# 07_-_SAMA7D65-PIO.net
KiCad netlist of a schematic drawn in Altium Designer
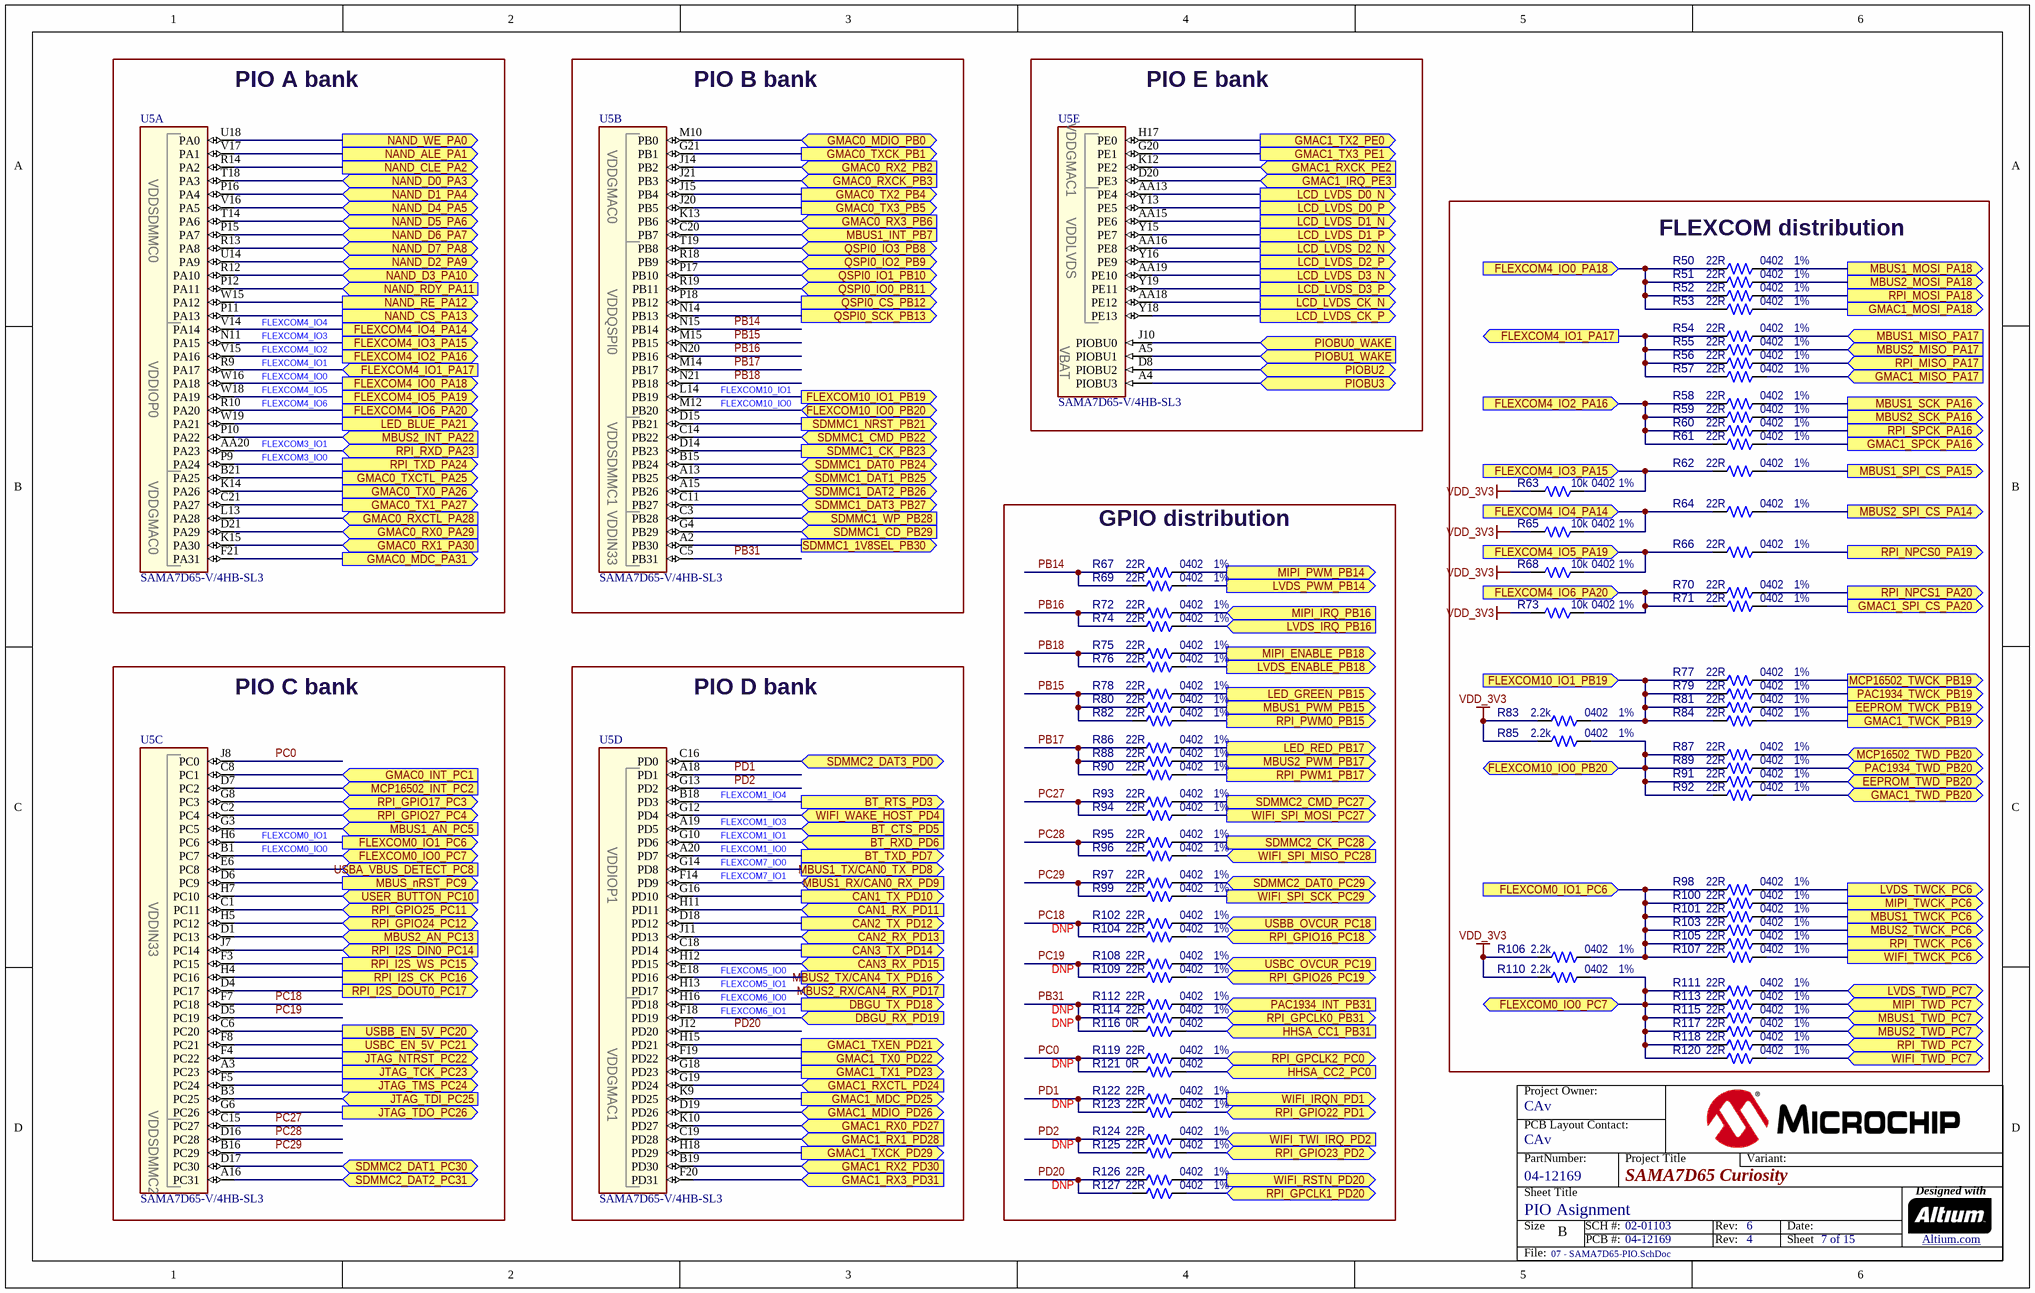
[diagram p0: 07 - SAMA7D65-PIO.SchDoc]

(export (version "E")
  (design (tool "Eeschema 10.0.6"))
  (components
    (comp (ref "R50")
      (value "22R")
      (footprint "RES_C_0402")
      (description "Resistor")
      (fields
        (field (name "PACKAGE") "0402")
        (field (name "POWER") "1/10W")
        (field (name "TOLERANCE") "1%")
        (field (name "OWNER") "Mike Ragsdale")
      )
      (libsource (lib "") (part "Resistor_1"))
    )
    (comp (ref "R51")
      (value "22R")
      (footprint "RES_C_0402")
      (description "Resistor")
      (fields
        (field (name "PACKAGE") "0402")
        (field (name "POWER") "1/10W")
        (field (name "TOLERANCE") "1%")
        (field (name "OWNER") "Mike Ragsdale")
      )
      (libsource (lib "") (part "Resistor_1"))
    )
    (comp (ref "R52")
      (value "22R")
      (footprint "RES_C_0402")
      (description "Resistor")
      (fields
        (field (name "PACKAGE") "0402")
        (field (name "POWER") "1/10W")
        (field (name "TOLERANCE") "1%")
        (field (name "OWNER") "Mike Ragsdale")
      )
      (libsource (lib "") (part "Resistor_1"))
    )
    (comp (ref "R53")
      (value "22R")
      (footprint "RES_C_0402")
      (description "Resistor")
      (fields
        (field (name "PACKAGE") "0402")
        (field (name "POWER") "1/10W")
        (field (name "TOLERANCE") "1%")
        (field (name "OWNER") "Mike Ragsdale")
      )
      (libsource (lib "") (part "Resistor_1"))
    )
    (comp (ref "R54")
      (value "22R")
      (footprint "RES_C_0402")
      (description "Resistor")
      (fields
        (field (name "PACKAGE") "0402")
        (field (name "POWER") "1/10W")
        (field (name "TOLERANCE") "1%")
        (field (name "OWNER") "Mike Ragsdale")
      )
      (libsource (lib "") (part "Resistor_1"))
    )
    (comp (ref "R55")
      (value "22R")
      (footprint "RES_C_0402")
      (description "Resistor")
      (fields
        (field (name "PACKAGE") "0402")
        (field (name "POWER") "1/10W")
        (field (name "TOLERANCE") "1%")
        (field (name "OWNER") "Mike Ragsdale")
      )
      (libsource (lib "") (part "Resistor_1"))
    )
    (comp (ref "R56")
      (value "22R")
      (footprint "RES_C_0402")
      (description "Resistor")
      (fields
        (field (name "PACKAGE") "0402")
        (field (name "POWER") "1/10W")
        (field (name "TOLERANCE") "1%")
        (field (name "OWNER") "Mike Ragsdale")
      )
      (libsource (lib "") (part "Resistor_1"))
    )
    (comp (ref "R57")
      (value "22R")
      (footprint "RES_C_0402")
      (description "Resistor")
      (fields
        (field (name "PACKAGE") "0402")
        (field (name "POWER") "1/10W")
        (field (name "TOLERANCE") "1%")
        (field (name "OWNER") "Mike Ragsdale")
      )
      (libsource (lib "") (part "Resistor_1"))
    )
    (comp (ref "R58")
      (value "22R")
      (footprint "RES_C_0402")
      (description "Resistor")
      (fields
        (field (name "PACKAGE") "0402")
        (field (name "POWER") "1/10W")
        (field (name "TOLERANCE") "1%")
        (field (name "OWNER") "Mike Ragsdale")
      )
      (libsource (lib "") (part "Resistor_1"))
    )
    (comp (ref "R59")
      (value "22R")
      (footprint "RES_C_0402")
      (description "Resistor")
      (fields
        (field (name "PACKAGE") "0402")
        (field (name "POWER") "1/10W")
        (field (name "TOLERANCE") "1%")
        (field (name "OWNER") "Mike Ragsdale")
      )
      (libsource (lib "") (part "Resistor_1"))
    )
    (comp (ref "R60")
      (value "22R")
      (footprint "RES_C_0402")
      (description "Resistor")
      (fields
        (field (name "PACKAGE") "0402")
        (field (name "POWER") "1/10W")
        (field (name "TOLERANCE") "1%")
        (field (name "OWNER") "Mike Ragsdale")
      )
      (libsource (lib "") (part "Resistor_1"))
    )
    (comp (ref "R61")
      (value "22R")
      (footprint "RES_C_0402")
      (description "Resistor")
      (fields
        (field (name "PACKAGE") "0402")
        (field (name "POWER") "1/10W")
        (field (name "TOLERANCE") "1%")
        (field (name "OWNER") "Mike Ragsdale")
      )
      (libsource (lib "") (part "Resistor_1"))
    )
    (comp (ref "R62")
      (value "22R")
      (footprint "RES_C_0402")
      (description "Resistor")
      (fields
        (field (name "PACKAGE") "0402")
        (field (name "POWER") "1/10W")
        (field (name "TOLERANCE") "1%")
        (field (name "OWNER") "Mike Ragsdale")
      )
      (libsource (lib "") (part "Resistor_1"))
    )
    (comp (ref "R63")
      (value "10k")
      (footprint "RES_C_0402")
      (description "Resistor")
      (fields
        (field (name "PACKAGE") "0402")
        (field (name "TOLERANCE") "1%")
        (field (name "VOLTAGE") "50V")
        (field (name "POWER") "1/10W")
        (field (name "OWNER") "Brent Lanphear")
      )
      (libsource (lib "MCHP-CDB") (part "Resistor"))
    )
    (comp (ref "R64")
      (value "22R")
      (footprint "RES_C_0402")
      (description "Resistor")
      (fields
        (field (name "PACKAGE") "0402")
        (field (name "POWER") "1/10W")
        (field (name "TOLERANCE") "1%")
        (field (name "OWNER") "Mike Ragsdale")
      )
      (libsource (lib "") (part "Resistor_1"))
    )
    (comp (ref "R65")
      (value "10k")
      (footprint "RES_C_0402")
      (description "Resistor")
      (fields
        (field (name "PACKAGE") "0402")
        (field (name "TOLERANCE") "1%")
        (field (name "VOLTAGE") "50V")
        (field (name "POWER") "1/10W")
        (field (name "OWNER") "Brent Lanphear")
      )
      (libsource (lib "MCHP-CDB") (part "Resistor"))
    )
    (comp (ref "R66")
      (value "22R")
      (footprint "RES_C_0402")
      (description "Resistor")
      (fields
        (field (name "PACKAGE") "0402")
        (field (name "POWER") "1/10W")
        (field (name "TOLERANCE") "1%")
        (field (name "OWNER") "Mike Ragsdale")
      )
      (libsource (lib "") (part "Resistor_1"))
    )
    (comp (ref "R67")
      (value "22R")
      (footprint "RES_C_0402")
      (description "Resistor")
      (fields
        (field (name "PACKAGE") "0402")
        (field (name "POWER") "1/10W")
        (field (name "TOLERANCE") "1%")
        (field (name "OWNER") "Mike Ragsdale")
      )
      (libsource (lib "") (part "Resistor_1"))
    )
    (comp (ref "R68")
      (value "10k")
      (footprint "RES_C_0402")
      (description "Resistor")
      (fields
        (field (name "PACKAGE") "0402")
        (field (name "TOLERANCE") "1%")
        (field (name "VOLTAGE") "50V")
        (field (name "POWER") "1/10W")
        (field (name "OWNER") "Brent Lanphear")
      )
      (libsource (lib "MCHP-CDB") (part "Resistor"))
    )
    (comp (ref "R69")
      (value "22R")
      (footprint "RES_C_0402")
      (description "Resistor")
      (fields
        (field (name "PACKAGE") "0402")
        (field (name "POWER") "1/10W")
        (field (name "TOLERANCE") "1%")
        (field (name "OWNER") "Mike Ragsdale")
      )
      (libsource (lib "") (part "Resistor_1"))
    )
    (comp (ref "R70")
      (value "22R")
      (footprint "RES_C_0402")
      (description "Resistor")
      (fields
        (field (name "PACKAGE") "0402")
        (field (name "POWER") "1/10W")
        (field (name "TOLERANCE") "1%")
        (field (name "OWNER") "Mike Ragsdale")
      )
      (libsource (lib "") (part "Resistor_1"))
    )
    (comp (ref "R71")
      (value "22R")
      (footprint "RES_C_0402")
      (description "Resistor")
      (fields
        (field (name "PACKAGE") "0402")
        (field (name "POWER") "1/10W")
        (field (name "TOLERANCE") "1%")
        (field (name "OWNER") "Mike Ragsdale")
      )
      (libsource (lib "") (part "Resistor_1"))
    )
    (comp (ref "R72")
      (value "22R")
      (footprint "RES_C_0402")
      (description "Resistor")
      (fields
        (field (name "PACKAGE") "0402")
        (field (name "POWER") "1/10W")
        (field (name "TOLERANCE") "1%")
        (field (name "OWNER") "Mike Ragsdale")
      )
      (libsource (lib "") (part "Resistor_1"))
    )
    (comp (ref "R73")
      (value "10k")
      (footprint "RES_C_0402")
      (description "Resistor")
      (fields
        (field (name "PACKAGE") "0402")
        (field (name "TOLERANCE") "1%")
        (field (name "VOLTAGE") "50V")
        (field (name "POWER") "1/10W")
        (field (name "OWNER") "Brent Lanphear")
      )
      (libsource (lib "MCHP-CDB") (part "Resistor"))
    )
    (comp (ref "R74")
      (value "22R")
      (footprint "RES_C_0402")
      (description "Resistor")
      (fields
        (field (name "PACKAGE") "0402")
        (field (name "POWER") "1/10W")
        (field (name "TOLERANCE") "1%")
        (field (name "OWNER") "Mike Ragsdale")
      )
      (libsource (lib "") (part "Resistor_1"))
    )
    (comp (ref "R75")
      (value "22R")
      (footprint "RES_C_0402")
      (description "Resistor")
      (fields
        (field (name "PACKAGE") "0402")
        (field (name "POWER") "1/10W")
        (field (name "TOLERANCE") "1%")
        (field (name "OWNER") "Mike Ragsdale")
      )
      (libsource (lib "") (part "Resistor_1"))
    )
    (comp (ref "R76")
      (value "22R")
      (footprint "RES_C_0402")
      (description "Resistor")
      (fields
        (field (name "PACKAGE") "0402")
        (field (name "POWER") "1/10W")
        (field (name "TOLERANCE") "1%")
        (field (name "OWNER") "Mike Ragsdale")
      )
      (libsource (lib "") (part "Resistor_1"))
    )
    (comp (ref "R77")
      (value "22R")
      (footprint "RES_C_0402")
      (description "Resistor")
      (fields
        (field (name "PACKAGE") "0402")
        (field (name "POWER") "1/10W")
        (field (name "TOLERANCE") "1%")
        (field (name "OWNER") "Mike Ragsdale")
      )
      (libsource (lib "") (part "Resistor_1"))
    )
    (comp (ref "R78")
      (value "22R")
      (footprint "RES_C_0402")
      (description "Resistor")
      (fields
        (field (name "PACKAGE") "0402")
        (field (name "POWER") "1/10W")
        (field (name "TOLERANCE") "1%")
        (field (name "OWNER") "Mike Ragsdale")
      )
      (libsource (lib "") (part "Resistor_1"))
    )
    (comp (ref "R79")
      (value "22R")
      (footprint "RES_C_0402")
      (description "Resistor")
      (fields
        (field (name "PACKAGE") "0402")
        (field (name "POWER") "1/10W")
        (field (name "TOLERANCE") "1%")
        (field (name "OWNER") "Mike Ragsdale")
      )
      (libsource (lib "") (part "Resistor_1"))
    )
    (comp (ref "R80")
      (value "22R")
      (footprint "RES_C_0402")
      (description "Resistor")
      (fields
        (field (name "PACKAGE") "0402")
        (field (name "POWER") "1/10W")
        (field (name "TOLERANCE") "1%")
        (field (name "OWNER") "Mike Ragsdale")
      )
      (libsource (lib "") (part "Resistor_1"))
    )
    (comp (ref "R81")
      (value "22R")
      (footprint "RES_C_0402")
      (description "Resistor")
      (fields
        (field (name "PACKAGE") "0402")
        (field (name "POWER") "1/10W")
        (field (name "TOLERANCE") "1%")
        (field (name "OWNER") "Mike Ragsdale")
      )
      (libsource (lib "") (part "Resistor_1"))
    )
    (comp (ref "R82")
      (value "22R")
      (footprint "RES_C_0402")
      (description "Resistor")
      (fields
        (field (name "PACKAGE") "0402")
        (field (name "POWER") "1/10W")
        (field (name "TOLERANCE") "1%")
        (field (name "OWNER") "Mike Ragsdale")
      )
      (libsource (lib "") (part "Resistor_1"))
    )
    (comp (ref "R83")
      (value "2.2k")
      (footprint "RES_C_0402")
      (description "Resistor")
      (fields
        (field (name "PACKAGE") "0402")
        (field (name "POWER") "1/10W")
        (field (name "TOLERANCE") "1%")
        (field (name "VOLTAGE") "50V")
        (field (name "OWNER") "Tad Ahlvers")
      )
      (libsource (lib "") (part "Resistor_1"))
    )
    (comp (ref "R84")
      (value "22R")
      (footprint "RES_C_0402")
      (description "Resistor")
      (fields
        (field (name "PACKAGE") "0402")
        (field (name "POWER") "1/10W")
        (field (name "TOLERANCE") "1%")
        (field (name "OWNER") "Mike Ragsdale")
      )
      (libsource (lib "") (part "Resistor_1"))
    )
    (comp (ref "R85")
      (value "2.2k")
      (footprint "RES_C_0402")
      (description "Resistor")
      (fields
        (field (name "PACKAGE") "0402")
        (field (name "POWER") "1/10W")
        (field (name "TOLERANCE") "1%")
        (field (name "VOLTAGE") "50V")
        (field (name "OWNER") "Tad Ahlvers")
      )
      (libsource (lib "") (part "Resistor_1"))
    )
    (comp (ref "R86")
      (value "22R")
      (footprint "RES_C_0402")
      (description "Resistor")
      (fields
        (field (name "PACKAGE") "0402")
        (field (name "POWER") "1/10W")
        (field (name "TOLERANCE") "1%")
        (field (name "OWNER") "Mike Ragsdale")
      )
      (libsource (lib "") (part "Resistor_1"))
    )
    (comp (ref "R87")
      (value "22R")
      (footprint "RES_C_0402")
      (description "Resistor")
      (fields
        (field (name "PACKAGE") "0402")
        (field (name "POWER") "1/10W")
        (field (name "TOLERANCE") "1%")
        (field (name "OWNER") "Mike Ragsdale")
      )
      (libsource (lib "") (part "Resistor_1"))
    )
    (comp (ref "R88")
      (value "22R")
      (footprint "RES_C_0402")
      (description "Resistor")
      (fields
        (field (name "PACKAGE") "0402")
        (field (name "POWER") "1/10W")
        (field (name "TOLERANCE") "1%")
        (field (name "OWNER") "Mike Ragsdale")
      )
      (libsource (lib "") (part "Resistor_1"))
    )
    (comp (ref "R89")
      (value "22R")
      (footprint "RES_C_0402")
      (description "Resistor")
      (fields
        (field (name "PACKAGE") "0402")
        (field (name "POWER") "1/10W")
        (field (name "TOLERANCE") "1%")
        (field (name "OWNER") "Mike Ragsdale")
      )
      (libsource (lib "") (part "Resistor_1"))
    )
    (comp (ref "R90")
      (value "22R")
      (footprint "RES_C_0402")
      (description "Resistor")
      (fields
        (field (name "PACKAGE") "0402")
        (field (name "POWER") "1/10W")
        (field (name "TOLERANCE") "1%")
        (field (name "OWNER") "Mike Ragsdale")
      )
      (libsource (lib "") (part "Resistor_1"))
    )
    (comp (ref "R91")
      (value "22R")
      (footprint "RES_C_0402")
      (description "Resistor")
      (fields
        (field (name "PACKAGE") "0402")
        (field (name "POWER") "1/10W")
        (field (name "TOLERANCE") "1%")
        (field (name "OWNER") "Mike Ragsdale")
      )
      (libsource (lib "") (part "Resistor_1"))
    )
    (comp (ref "R92")
      (value "22R")
      (footprint "RES_C_0402")
      (description "Resistor")
      (fields
        (field (name "PACKAGE") "0402")
        (field (name "POWER") "1/10W")
        (field (name "TOLERANCE") "1%")
        (field (name "OWNER") "Mike Ragsdale")
      )
      (libsource (lib "") (part "Resistor_1"))
    )
    (comp (ref "R93")
      (value "22R")
      (footprint "RES_C_0402")
      (description "Resistor")
      (fields
        (field (name "PACKAGE") "0402")
        (field (name "POWER") "1/10W")
        (field (name "TOLERANCE") "1%")
        (field (name "OWNER") "Mike Ragsdale")
      )
      (libsource (lib "") (part "Resistor_1"))
    )
    (comp (ref "R94")
      (value "22R")
      (footprint "RES_C_0402")
      (description "Resistor")
      (fields
        (field (name "PACKAGE") "0402")
        (field (name "POWER") "1/10W")
        (field (name "TOLERANCE") "1%")
        (field (name "OWNER") "Mike Ragsdale")
      )
      (libsource (lib "") (part "Resistor_1"))
    )
    (comp (ref "R95")
      (value "22R")
      (footprint "RES_C_0402")
      (description "Resistor")
      (fields
        (field (name "PACKAGE") "0402")
        (field (name "POWER") "1/10W")
        (field (name "TOLERANCE") "1%")
        (field (name "OWNER") "Mike Ragsdale")
      )
      (libsource (lib "") (part "Resistor_1"))
    )
    (comp (ref "R96")
      (value "22R")
      (footprint "RES_C_0402")
      (description "Resistor")
      (fields
        (field (name "PACKAGE") "0402")
        (field (name "POWER") "1/10W")
        (field (name "TOLERANCE") "1%")
        (field (name "OWNER") "Mike Ragsdale")
      )
      (libsource (lib "") (part "Resistor_1"))
    )
    (comp (ref "R97")
      (value "22R")
      (footprint "RES_C_0402")
      (description "Resistor")
      (fields
        (field (name "PACKAGE") "0402")
        (field (name "POWER") "1/10W")
        (field (name "TOLERANCE") "1%")
        (field (name "OWNER") "Mike Ragsdale")
      )
      (libsource (lib "") (part "Resistor_1"))
    )
    (comp (ref "R98")
      (value "22R")
      (footprint "RES_C_0402")
      (description "Resistor")
      (fields
        (field (name "PACKAGE") "0402")
        (field (name "POWER") "1/10W")
        (field (name "TOLERANCE") "1%")
        (field (name "OWNER") "Mike Ragsdale")
      )
      (libsource (lib "") (part "Resistor_1"))
    )
    (comp (ref "R99")
      (value "22R")
      (footprint "RES_C_0402")
      (description "Resistor")
      (fields
        (field (name "PACKAGE") "0402")
        (field (name "POWER") "1/10W")
        (field (name "TOLERANCE") "1%")
        (field (name "OWNER") "Mike Ragsdale")
      )
      (libsource (lib "") (part "Resistor_1"))
    )
    (comp (ref "R100")
      (value "22R")
      (footprint "RES_C_0402")
      (description "Resistor")
      (fields
        (field (name "PACKAGE") "0402")
        (field (name "POWER") "1/10W")
        (field (name "TOLERANCE") "1%")
        (field (name "OWNER") "Mike Ragsdale")
      )
      (libsource (lib "") (part "Resistor_1"))
    )
    (comp (ref "R101")
      (value "22R")
      (footprint "RES_C_0402")
      (description "Resistor")
      (fields
        (field (name "PACKAGE") "0402")
        (field (name "POWER") "1/10W")
        (field (name "TOLERANCE") "1%")
        (field (name "OWNER") "Mike Ragsdale")
      )
      (libsource (lib "") (part "Resistor_1"))
    )
    (comp (ref "R102")
      (value "22R")
      (footprint "RES_C_0402")
      (description "Resistor")
      (fields
        (field (name "PACKAGE") "0402")
        (field (name "POWER") "1/10W")
        (field (name "TOLERANCE") "1%")
        (field (name "OWNER") "Mike Ragsdale")
      )
      (libsource (lib "") (part "Resistor_1"))
    )
    (comp (ref "R103")
      (value "22R")
      (footprint "RES_C_0402")
      (description "Resistor")
      (fields
        (field (name "PACKAGE") "0402")
        (field (name "POWER") "1/10W")
        (field (name "TOLERANCE") "1%")
        (field (name "OWNER") "Mike Ragsdale")
      )
      (libsource (lib "") (part "Resistor_1"))
    )
    (comp (ref "R104")
      (value "22R")
      (footprint "RES_C_0402")
      (description "Resistor")
      (fields
        (field (name "PACKAGE") "0402")
        (field (name "POWER") "1/10W")
        (field (name "POPULATED") "DNP")
        (field (name "TOLERANCE") "1%")
        (field (name "OWNER") "Mike Ragsdale")
      )
      (libsource (lib "") (part "Resistor_1"))
    )
    (comp (ref "R105")
      (value "22R")
      (footprint "RES_C_0402")
      (description "Resistor")
      (fields
        (field (name "PACKAGE") "0402")
        (field (name "POWER") "1/10W")
        (field (name "TOLERANCE") "1%")
        (field (name "OWNER") "Mike Ragsdale")
      )
      (libsource (lib "") (part "Resistor_1"))
    )
    (comp (ref "R106")
      (value "2.2k")
      (footprint "RES_C_0402")
      (description "Resistor")
      (fields
        (field (name "PACKAGE") "0402")
        (field (name "POWER") "1/10W")
        (field (name "TOLERANCE") "1%")
        (field (name "VOLTAGE") "50V")
        (field (name "OWNER") "Tad Ahlvers")
      )
      (libsource (lib "") (part "Resistor_1"))
    )
    (comp (ref "R107")
      (value "22R")
      (footprint "RES_C_0402")
      (description "Resistor")
      (fields
        (field (name "PACKAGE") "0402")
        (field (name "POWER") "1/10W")
        (field (name "TOLERANCE") "1%")
        (field (name "OWNER") "Mike Ragsdale")
      )
      (libsource (lib "") (part "Resistor_1"))
    )
    (comp (ref "R108")
      (value "22R")
      (footprint "RES_C_0402")
      (description "Resistor")
      (fields
        (field (name "PACKAGE") "0402")
        (field (name "POWER") "1/10W")
        (field (name "TOLERANCE") "1%")
        (field (name "OWNER") "Mike Ragsdale")
      )
      (libsource (lib "") (part "Resistor_1"))
    )
    (comp (ref "R109")
      (value "22R")
      (footprint "RES_C_0402")
      (description "Resistor")
      (fields
        (field (name "PACKAGE") "0402")
        (field (name "POWER") "1/10W")
        (field (name "POPULATED") "DNP")
        (field (name "TOLERANCE") "1%")
        (field (name "OWNER") "Mike Ragsdale")
      )
      (libsource (lib "") (part "Resistor_1"))
    )
    (comp (ref "R110")
      (value "2.2k")
      (footprint "RES_C_0402")
      (description "Resistor")
      (fields
        (field (name "PACKAGE") "0402")
        (field (name "POWER") "1/10W")
        (field (name "TOLERANCE") "1%")
        (field (name "VOLTAGE") "50V")
        (field (name "OWNER") "Tad Ahlvers")
      )
      (libsource (lib "") (part "Resistor_1"))
    )
    (comp (ref "R111")
      (value "22R")
      (footprint "RES_C_0402")
      (description "Resistor")
      (fields
        (field (name "PACKAGE") "0402")
        (field (name "POWER") "1/10W")
        (field (name "TOLERANCE") "1%")
        (field (name "OWNER") "Mike Ragsdale")
      )
      (libsource (lib "") (part "Resistor_1"))
    )
    (comp (ref "R112")
      (value "22R")
      (footprint "RES_C_0402")
      (description "Resistor")
      (fields
        (field (name "PACKAGE") "0402")
        (field (name "POWER") "1/10W")
        (field (name "TOLERANCE") "1%")
        (field (name "OWNER") "Mike Ragsdale")
      )
      (libsource (lib "") (part "Resistor_1"))
    )
    (comp (ref "R113")
      (value "22R")
      (footprint "RES_C_0402")
      (description "Resistor")
      (fields
        (field (name "PACKAGE") "0402")
        (field (name "POWER") "1/10W")
        (field (name "TOLERANCE") "1%")
        (field (name "OWNER") "Mike Ragsdale")
      )
      (libsource (lib "") (part "Resistor_1"))
    )
    (comp (ref "R114")
      (value "22R")
      (footprint "RES_C_0402")
      (description "Resistor")
      (fields
        (field (name "PACKAGE") "0402")
        (field (name "POWER") "1/10W")
        (field (name "POPULATED") "DNP")
        (field (name "TOLERANCE") "1%")
        (field (name "OWNER") "Mike Ragsdale")
      )
      (libsource (lib "") (part "Resistor_1"))
    )
    (comp (ref "R115")
      (value "22R")
      (footprint "RES_C_0402")
      (description "Resistor")
      (fields
        (field (name "PACKAGE") "0402")
        (field (name "POWER") "1/10W")
        (field (name "TOLERANCE") "1%")
        (field (name "OWNER") "Mike Ragsdale")
      )
      (libsource (lib "") (part "Resistor_1"))
    )
    (comp (ref "R116")
      (value "0R")
      (footprint "RES_C_0402")
      (description "Resistor")
      (fields
        (field (name "PACKAGE") "0402")
        (field (name "POWER") "1/16W")
        (field (name "POPULATED") "DNP")
        (field (name "OWNER") "Sompoch Loboonlert")
      )
      (libsource (lib "") (part "Resistor_1"))
    )
    (comp (ref "R117")
      (value "22R")
      (footprint "RES_C_0402")
      (description "Resistor")
      (fields
        (field (name "PACKAGE") "0402")
        (field (name "POWER") "1/10W")
        (field (name "TOLERANCE") "1%")
        (field (name "OWNER") "Mike Ragsdale")
      )
      (libsource (lib "") (part "Resistor_1"))
    )
    (comp (ref "R118")
      (value "22R")
      (footprint "RES_C_0402")
      (description "Resistor")
      (fields
        (field (name "PACKAGE") "0402")
        (field (name "POWER") "1/10W")
        (field (name "TOLERANCE") "1%")
        (field (name "OWNER") "Mike Ragsdale")
      )
      (libsource (lib "") (part "Resistor_1"))
    )
    (comp (ref "R119")
      (value "22R")
      (footprint "RES_C_0402")
      (description "Resistor")
      (fields
        (field (name "PACKAGE") "0402")
        (field (name "POWER") "1/10W")
        (field (name "TOLERANCE") "1%")
        (field (name "OWNER") "Mike Ragsdale")
      )
      (libsource (lib "") (part "Resistor_1"))
    )
    (comp (ref "R120")
      (value "22R")
      (footprint "RES_C_0402")
      (description "Resistor")
      (fields
        (field (name "PACKAGE") "0402")
        (field (name "POWER") "1/10W")
        (field (name "TOLERANCE") "1%")
        (field (name "OWNER") "Mike Ragsdale")
      )
      (libsource (lib "") (part "Resistor_1"))
    )
    (comp (ref "R121")
      (value "0R")
      (footprint "RES_C_0402")
      (description "Resistor")
      (fields
        (field (name "PACKAGE") "0402")
        (field (name "POWER") "1/16W")
        (field (name "POPULATED") "DNP")
        (field (name "OWNER") "Sompoch Loboonlert")
      )
      (libsource (lib "") (part "Resistor_1"))
    )
    (comp (ref "R122")
      (value "22R")
      (footprint "RES_C_0402")
      (description "Resistor")
      (fields
        (field (name "PACKAGE") "0402")
        (field (name "POWER") "1/10W")
        (field (name "TOLERANCE") "1%")
        (field (name "OWNER") "Mike Ragsdale")
      )
      (libsource (lib "") (part "Resistor_1"))
    )
    (comp (ref "R123")
      (value "22R")
      (footprint "RES_C_0402")
      (description "Resistor")
      (fields
        (field (name "PACKAGE") "0402")
        (field (name "POWER") "1/10W")
        (field (name "POPULATED") "DNP")
        (field (name "TOLERANCE") "1%")
        (field (name "OWNER") "Mike Ragsdale")
      )
      (libsource (lib "") (part "Resistor_1"))
    )
    (comp (ref "R124")
      (value "22R")
      (footprint "RES_C_0402")
      (description "Resistor")
      (fields
        (field (name "PACKAGE") "0402")
        (field (name "POWER") "1/10W")
        (field (name "TOLERANCE") "1%")
        (field (name "OWNER") "Mike Ragsdale")
      )
      (libsource (lib "") (part "Resistor_1"))
    )
    (comp (ref "R125")
      (value "22R")
      (footprint "RES_C_0402")
      (description "Resistor")
      (fields
        (field (name "PACKAGE") "0402")
        (field (name "POWER") "1/10W")
        (field (name "POPULATED") "DNP")
        (field (name "TOLERANCE") "1%")
        (field (name "OWNER") "Mike Ragsdale")
      )
      (libsource (lib "") (part "Resistor_1"))
    )
    (comp (ref "R126")
      (value "22R")
      (footprint "RES_C_0402")
      (description "Resistor")
      (fields
        (field (name "PACKAGE") "0402")
        (field (name "POWER") "1/10W")
        (field (name "TOLERANCE") "1%")
        (field (name "OWNER") "Mike Ragsdale")
      )
      (libsource (lib "") (part "Resistor_1"))
    )
    (comp (ref "R127")
      (value "22R")
      (footprint "RES_C_0402")
      (description "Resistor")
      (fields
        (field (name "PACKAGE") "0402")
        (field (name "POWER") "1/10W")
        (field (name "POPULATED") "DNP")
        (field (name "TOLERANCE") "1%")
        (field (name "OWNER") "Mike Ragsdale")
      )
      (libsource (lib "") (part "Resistor_1"))
    )
    (comp (ref "U5")
      (value "SAMA7D65-V/4HB-SL3")
      (footprint "TFBGA-343_14x14")
      (description "SAMA7D65 MPU 1000MHz Cortex-A7 TFBGA-343")
      (fields (field (name "Comment") "SAMA7D65") (field (name "OWNER") "Ciprian Abramov"))
      (libsource (lib "MCHP-CDB") (part "SAMA7D65-TFBGA-343"))
    )
  )
  (nets
    (net (code "1") (name "/BT_CTS_PD5") (class "Default")
      (node (ref "U5") (pin "A19") (pinfunction "PD5_A19") (pintype "bidirectional"))
    )
    (net (code "2") (name "/BT_RTS_PD3") (class "Default")
      (node (ref "U5") (pin "B18") (pinfunction "PD3_B18") (pintype "bidirectional"))
    )
    (net (code "3") (name "/BT_RXD_PD6") (class "Default")
      (node (ref "U5") (pin "G10") (pinfunction "PD6_G10") (pintype "bidirectional"))
    )
    (net (code "4") (name "/BT_TXD_PD7") (class "Default")
      (node (ref "U5") (pin "A20") (pinfunction "PD7_A20") (pintype "bidirectional"))
    )
    (net (code "5") (name "/CAN1_RX_PD11") (class "Default")
      (node (ref "U5") (pin "H11") (pinfunction "PD11_H11") (pintype "bidirectional"))
    )
    (net (code "6") (name "/CAN1_TX_PD10") (class "Default")
      (node (ref "U5") (pin "G16") (pinfunction "PD10_G16") (pintype "bidirectional"))
    )
    (net (code "7") (name "/CAN2_RX_PD13") (class "Default")
      (node (ref "U5") (pin "J11") (pinfunction "PD13_J11") (pintype "bidirectional"))
    )
    (net (code "8") (name "/CAN2_TX_PD12") (class "Default")
      (node (ref "U5") (pin "D18") (pinfunction "PD12_D18") (pintype "bidirectional"))
    )
    (net (code "9") (name "/CAN3_RX_PD15") (class "Default")
      (node (ref "U5") (pin "H12") (pinfunction "PD15_H12") (pintype "bidirectional"))
    )
    (net (code "10") (name "/CAN3_TX_PD14") (class "Default")
      (node (ref "U5") (pin "C18") (pinfunction "PD14_C18") (pintype "bidirectional"))
    )
    (net (code "11") (name "/DBGU_RX_PD19") (class "Default")
      (node (ref "U5") (pin "F18") (pinfunction "PD19_F18") (pintype "bidirectional"))
    )
    (net (code "12") (name "/DBGU_TX_PD18") (class "Default")
      (node (ref "U5") (pin "H16") (pinfunction "PD18_H16") (pintype "bidirectional"))
    )
    (net (code "13") (name "/EEPROM_TWCK_PB19") (class "Default")
      (node (ref "R81") (pin "2") (pinfunction "2_2") (pintype "passive"))
    )
    (net (code "14") (name "/EEPROM_TWD_PB20") (class "Default")
      (node (ref "R91") (pin "2") (pinfunction "2_2") (pintype "passive"))
    )
    (net (code "15") (name "/FLEXCOM0_IO0_PC7") (class "Default")
      (node (ref "R110") (pin "2") (pinfunction "2_2") (pintype "passive"))
      (node (ref "R111") (pin "1") (pinfunction "1_1") (pintype "passive"))
      (node (ref "R113") (pin "1") (pinfunction "1_1") (pintype "passive"))
      (node (ref "R115") (pin "1") (pinfunction "1_1") (pintype "passive"))
      (node (ref "R117") (pin "1") (pinfunction "1_1") (pintype "passive"))
      (node (ref "R118") (pin "1") (pinfunction "1_1") (pintype "passive"))
      (node (ref "R120") (pin "1") (pinfunction "1_1") (pintype "passive"))
      (node (ref "U5") (pin "B1") (pinfunction "PC7_B1") (pintype "bidirectional"))
    )
    (net (code "16") (name "/FLEXCOM0_IO1_PC6") (class "Default")
      (node (ref "R100") (pin "1") (pinfunction "1_1") (pintype "passive"))
      (node (ref "R101") (pin "1") (pinfunction "1_1") (pintype "passive"))
      (node (ref "R103") (pin "1") (pinfunction "1_1") (pintype "passive"))
      (node (ref "R105") (pin "1") (pinfunction "1_1") (pintype "passive"))
      (node (ref "R106") (pin "2") (pinfunction "2_2") (pintype "passive"))
      (node (ref "R107") (pin "1") (pinfunction "1_1") (pintype "passive"))
      (node (ref "R98") (pin "1") (pinfunction "1_1") (pintype "passive"))
      (node (ref "U5") (pin "H6") (pinfunction "PC6_H6") (pintype "bidirectional"))
    )
    (net (code "17") (name "/FLEXCOM4_IO0_PA18") (class "Default")
      (node (ref "R50") (pin "1") (pinfunction "1_1") (pintype "passive"))
      (node (ref "R51") (pin "1") (pinfunction "1_1") (pintype "passive"))
      (node (ref "R52") (pin "1") (pinfunction "1_1") (pintype "passive"))
      (node (ref "R53") (pin "1") (pinfunction "1_1") (pintype "passive"))
      (node (ref "U5") (pin "W16") (pinfunction "PA18_W16") (pintype "bidirectional"))
    )
    (net (code "18") (name "/FLEXCOM4_IO1_PA17") (class "Default")
      (node (ref "R54") (pin "1") (pinfunction "1_1") (pintype "passive"))
      (node (ref "R55") (pin "1") (pinfunction "1_1") (pintype "passive"))
      (node (ref "R56") (pin "1") (pinfunction "1_1") (pintype "passive"))
      (node (ref "R57") (pin "1") (pinfunction "1_1") (pintype "passive"))
      (node (ref "U5") (pin "R9") (pinfunction "PA17_R9") (pintype "bidirectional"))
    )
    (net (code "19") (name "/FLEXCOM4_IO2_PA16") (class "Default")
      (node (ref "R58") (pin "1") (pinfunction "1_1") (pintype "passive"))
      (node (ref "R59") (pin "1") (pinfunction "1_1") (pintype "passive"))
      (node (ref "R60") (pin "1") (pinfunction "1_1") (pintype "passive"))
      (node (ref "R61") (pin "1") (pinfunction "1_1") (pintype "passive"))
      (node (ref "U5") (pin "V15") (pinfunction "PA16_V15") (pintype "bidirectional"))
    )
    (net (code "20") (name "/FLEXCOM4_IO3_PA15") (class "Default")
      (node (ref "R62") (pin "1") (pinfunction "1_1") (pintype "passive"))
      (node (ref "R63") (pin "1") (pinfunction "1_1") (pintype "passive"))
      (node (ref "U5") (pin "N11") (pinfunction "PA15_N11") (pintype "bidirectional"))
    )
    (net (code "21") (name "/FLEXCOM4_IO4_PA14") (class "Default")
      (node (ref "R64") (pin "1") (pinfunction "1_1") (pintype "passive"))
      (node (ref "R65") (pin "1") (pinfunction "1_1") (pintype "passive"))
      (node (ref "U5") (pin "V14") (pinfunction "PA14_V14") (pintype "bidirectional"))
    )
    (net (code "22") (name "/FLEXCOM4_IO5_PA19") (class "Default")
      (node (ref "R66") (pin "1") (pinfunction "1_1") (pintype "passive"))
      (node (ref "R68") (pin "1") (pinfunction "1_1") (pintype "passive"))
      (node (ref "U5") (pin "W18") (pinfunction "PA19_W18") (pintype "bidirectional"))
    )
    (net (code "23") (name "/FLEXCOM4_IO6_PA20") (class "Default")
      (node (ref "R70") (pin "1") (pinfunction "1_1") (pintype "passive"))
      (node (ref "R71") (pin "1") (pinfunction "1_1") (pintype "passive"))
      (node (ref "R73") (pin "1") (pinfunction "1_1") (pintype "passive"))
      (node (ref "U5") (pin "R10") (pinfunction "PA20_R10") (pintype "bidirectional"))
    )
    (net (code "24") (name "/FLEXCOM10_IO0_PB20") (class "Default")
      (node (ref "R85") (pin "2") (pinfunction "2_2") (pintype "passive"))
      (node (ref "R87") (pin "1") (pinfunction "1_1") (pintype "passive"))
      (node (ref "R89") (pin "1") (pinfunction "1_1") (pintype "passive"))
      (node (ref "R91") (pin "1") (pinfunction "1_1") (pintype "passive"))
      (node (ref "R92") (pin "1") (pinfunction "1_1") (pintype "passive"))
      (node (ref "U5") (pin "M12") (pinfunction "PB20_M12") (pintype "bidirectional"))
    )
    (net (code "25") (name "/FLEXCOM10_IO1_PB19") (class "Default")
      (node (ref "R77") (pin "1") (pinfunction "1_1") (pintype "passive"))
      (node (ref "R79") (pin "1") (pinfunction "1_1") (pintype "passive"))
      (node (ref "R81") (pin "1") (pinfunction "1_1") (pintype "passive"))
      (node (ref "R83") (pin "2") (pinfunction "2_2") (pintype "passive"))
      (node (ref "R84") (pin "1") (pinfunction "1_1") (pintype "passive"))
      (node (ref "U5") (pin "L14") (pinfunction "PB19_L14") (pintype "bidirectional"))
    )
    (net (code "26") (name "/GMAC0_INT_PC1") (class "Default")
      (node (ref "U5") (pin "C8") (pinfunction "PC1_C8") (pintype "bidirectional"))
    )
    (net (code "27") (name "/GMAC0_MDC_PA31") (class "Default")
      (node (ref "U5") (pin "F21") (pinfunction "PA31_F21") (pintype "bidirectional"))
    )
    (net (code "28") (name "/GMAC0_MDIO_PB0") (class "Default")
      (node (ref "U5") (pin "M10") (pinfunction "PB0_M10") (pintype "bidirectional"))
    )
    (net (code "29") (name "/GMAC0_RX0_PA29") (class "Default")
      (node (ref "U5") (pin "D21") (pinfunction "PA29_D21") (pintype "bidirectional"))
    )
    (net (code "30") (name "/GMAC0_RX1_PA30") (class "Default")
      (node (ref "U5") (pin "K15") (pinfunction "PA30_K15") (pintype "bidirectional"))
    )
    (net (code "31") (name "/GMAC0_RX2_PB2") (class "Default")
      (node (ref "U5") (pin "J14") (pinfunction "PB2_J14") (pintype "bidirectional"))
    )
    (net (code "32") (name "/GMAC0_RX3_PB6") (class "Default")
      (node (ref "U5") (pin "K13") (pinfunction "PB6_K13") (pintype "bidirectional"))
    )
    (net (code "33") (name "/GMAC0_RXCK_PB3") (class "Default")
      (node (ref "U5") (pin "J21") (pinfunction "PB3_J21") (pintype "bidirectional"))
    )
    (net (code "34") (name "/GMAC0_RXCTL_PA28") (class "Default")
      (node (ref "U5") (pin "L13") (pinfunction "PA28_L13") (pintype "bidirectional"))
    )
    (net (code "35") (name "/GMAC0_TX0_PA26") (class "Default")
      (node (ref "U5") (pin "K14") (pinfunction "PA26_K14") (pintype "bidirectional"))
    )
    (net (code "36") (name "/GMAC0_TX1_PA27") (class "Default")
      (node (ref "U5") (pin "C21") (pinfunction "PA27_C21") (pintype "bidirectional"))
    )
    (net (code "37") (name "/GMAC0_TX2_PB4") (class "Default")
      (node (ref "U5") (pin "J15") (pinfunction "PB4_J15") (pintype "bidirectional"))
    )
    (net (code "38") (name "/GMAC0_TX3_PB5") (class "Default")
      (node (ref "U5") (pin "J20") (pinfunction "PB5_J20") (pintype "bidirectional"))
    )
    (net (code "39") (name "/GMAC0_TXCK_PB1") (class "Default")
      (node (ref "U5") (pin "G21") (pinfunction "PB1_G21") (pintype "bidirectional"))
    )
    (net (code "40") (name "/GMAC0_TXCTL_PA25") (class "Default")
      (node (ref "U5") (pin "B21") (pinfunction "PA25_B21") (pintype "bidirectional"))
    )
    (net (code "41") (name "/GMAC1_IRQ_PE3") (class "Default")
      (node (ref "U5") (pin "D20") (pinfunction "PE3_D20") (pintype "bidirectional"))
    )
    (net (code "42") (name "/GMAC1_MDC_PD25") (class "Default")
      (node (ref "U5") (pin "K9") (pinfunction "PD25_K9") (pintype "bidirectional"))
    )
    (net (code "43") (name "/GMAC1_MDIO_PD26") (class "Default")
      (node (ref "U5") (pin "D19") (pinfunction "PD26_D19") (pintype "bidirectional"))
    )
    (net (code "44") (name "/GMAC1_MISO_PA17") (class "Default")
      (node (ref "R57") (pin "2") (pinfunction "2_2") (pintype "passive"))
    )
    (net (code "45") (name "/GMAC1_MOSI_PA18") (class "Default")
      (node (ref "R53") (pin "2") (pinfunction "2_2") (pintype "passive"))
    )
    (net (code "46") (name "/GMAC1_RX0_PD27") (class "Default")
      (node (ref "U5") (pin "K10") (pinfunction "PD27_K10") (pintype "bidirectional"))
    )
    (net (code "47") (name "/GMAC1_RX1_PD28") (class "Default")
      (node (ref "U5") (pin "C19") (pinfunction "PD28_C19") (pintype "bidirectional"))
    )
    (net (code "48") (name "/GMAC1_RX2_PD30") (class "Default")
      (node (ref "U5") (pin "B19") (pinfunction "PD30_B19") (pintype "bidirectional"))
    )
    (net (code "49") (name "/GMAC1_RX3_PD31") (class "Default")
      (node (ref "U5") (pin "F20") (pinfunction "PD31_F20") (pintype "bidirectional"))
    )
    (net (code "50") (name "/GMAC1_RXCK_PE2") (class "Default")
      (node (ref "U5") (pin "K12") (pinfunction "PE2_K12") (pintype "bidirectional"))
    )
    (net (code "51") (name "/GMAC1_RXCTL_PD24") (class "Default")
      (node (ref "U5") (pin "G19") (pinfunction "PD24_G19") (pintype "bidirectional"))
    )
    (net (code "52") (name "/GMAC1_SPCK_PA16") (class "Default")
      (node (ref "R61") (pin "2") (pinfunction "2_2") (pintype "passive"))
    )
    (net (code "53") (name "/GMAC1_SPI_CS_PA20") (class "Default")
      (node (ref "R71") (pin "2") (pinfunction "2_2") (pintype "passive"))
    )
    (net (code "54") (name "/GMAC1_TWCK_PB19") (class "Default")
      (node (ref "R84") (pin "2") (pinfunction "2_2") (pintype "passive"))
    )
    (net (code "55") (name "/GMAC1_TWD_PB20") (class "Default")
      (node (ref "R92") (pin "2") (pinfunction "2_2") (pintype "passive"))
    )
    (net (code "56") (name "/GMAC1_TX0_PD22") (class "Default")
      (node (ref "U5") (pin "F19") (pinfunction "PD22_F19") (pintype "bidirectional"))
    )
    (net (code "57") (name "/GMAC1_TX1_PD23") (class "Default")
      (node (ref "U5") (pin "G18") (pinfunction "PD23_G18") (pintype "bidirectional"))
    )
    (net (code "58") (name "/GMAC1_TX2_PE0") (class "Default")
      (node (ref "U5") (pin "H17") (pinfunction "PE0_H17") (pintype "bidirectional"))
    )
    (net (code "59") (name "/GMAC1_TX3_PE1") (class "Default")
      (node (ref "U5") (pin "G20") (pinfunction "PE1_G20") (pintype "bidirectional"))
    )
    (net (code "60") (name "/GMAC1_TXCK_PD29") (class "Default")
      (node (ref "U5") (pin "H18") (pinfunction "PD29_H18") (pintype "bidirectional"))
    )
    (net (code "61") (name "/GMAC1_TXEN_PD21") (class "Default")
      (node (ref "U5") (pin "H15") (pinfunction "PD21_H15") (pintype "bidirectional"))
    )
    (net (code "62") (name "/HHSA_CC1_PB31") (class "Default")
      (node (ref "R116") (pin "1") (pinfunction "1_1") (pintype "passive"))
    )
    (net (code "63") (name "/HHSA_CC2_PC0") (class "Default")
      (node (ref "R121") (pin "1") (pinfunction "1_1") (pintype "passive"))
    )
    (net (code "64") (name "/JTAG_NTRST_PC22") (class "Default")
      (node (ref "U5") (pin "F4") (pinfunction "PC22_F4") (pintype "bidirectional"))
    )
    (net (code "65") (name "/JTAG_TCK_PC23") (class "Default")
      (node (ref "U5") (pin "A3") (pinfunction "PC23_A3") (pintype "bidirectional"))
    )
    (net (code "66") (name "/JTAG_TDI_PC25") (class "Default")
      (node (ref "U5") (pin "B3") (pinfunction "PC25_B3") (pintype "bidirectional"))
    )
    (net (code "67") (name "/JTAG_TDO_PC26") (class "Default")
      (node (ref "U5") (pin "G6") (pinfunction "PC26_G6") (pintype "bidirectional"))
    )
    (net (code "68") (name "/JTAG_TMS_PC24") (class "Default")
      (node (ref "U5") (pin "F5") (pinfunction "PC24_F5") (pintype "bidirectional"))
    )
    (net (code "69") (name "/LCD_LVDS_CK_N") (class "Default")
      (node (ref "U5") (pin "AA18") (pinfunction "PE12_AA18") (pintype "bidirectional"))
    )
    (net (code "70") (name "/LCD_LVDS_CK_P") (class "Default")
      (node (ref "U5") (pin "Y18") (pinfunction "PE13_Y18") (pintype "bidirectional"))
    )
    (net (code "71") (name "/LCD_LVDS_D0_N") (class "Default")
      (node (ref "U5") (pin "AA13") (pinfunction "PE4_AA13") (pintype "bidirectional"))
    )
    (net (code "72") (name "/LCD_LVDS_D0_P") (class "Default")
      (node (ref "U5") (pin "Y13") (pinfunction "PE5_Y13") (pintype "bidirectional"))
    )
    (net (code "73") (name "/LCD_LVDS_D1_N") (class "Default")
      (node (ref "U5") (pin "AA15") (pinfunction "PE6_AA15") (pintype "bidirectional"))
    )
    (net (code "74") (name "/LCD_LVDS_D1_P") (class "Default")
      (node (ref "U5") (pin "Y15") (pinfunction "PE7_Y15") (pintype "bidirectional"))
    )
    (net (code "75") (name "/LCD_LVDS_D2_N") (class "Default")
      (node (ref "U5") (pin "AA16") (pinfunction "PE8_AA16") (pintype "bidirectional"))
    )
    (net (code "76") (name "/LCD_LVDS_D2_P") (class "Default")
      (node (ref "U5") (pin "Y16") (pinfunction "PE9_Y16") (pintype "bidirectional"))
    )
    (net (code "77") (name "/LCD_LVDS_D3_N") (class "Default")
      (node (ref "U5") (pin "AA19") (pinfunction "PE10_AA19") (pintype "bidirectional"))
    )
    (net (code "78") (name "/LCD_LVDS_D3_P") (class "Default")
      (node (ref "U5") (pin "Y19") (pinfunction "PE11_Y19") (pintype "bidirectional"))
    )
    (net (code "79") (name "/LED_BLUE_PA21") (class "Default")
      (node (ref "U5") (pin "W19") (pinfunction "PA21_W19") (pintype "bidirectional"))
    )
    (net (code "80") (name "/LED_GREEN_PB15") (class "Default")
      (node (ref "R78") (pin "2") (pinfunction "2_2") (pintype "passive"))
    )
    (net (code "81") (name "/LED_RED_PB17") (class "Default")
      (node (ref "R86") (pin "2") (pinfunction "2_2") (pintype "passive"))
    )
    (net (code "82") (name "/LVDS_ENABLE_PB18") (class "Default")
      (node (ref "R76") (pin "2") (pinfunction "2_2") (pintype "passive"))
    )
    (net (code "83") (name "/LVDS_IRQ_PB16") (class "Default")
      (node (ref "R74") (pin "2") (pinfunction "2_2") (pintype "passive"))
    )
    (net (code "84") (name "/LVDS_PWM_PB14") (class "Default")
      (node (ref "R69") (pin "2") (pinfunction "2_2") (pintype "passive"))
    )
    (net (code "85") (name "/LVDS_TWCK_PC6") (class "Default")
      (node (ref "R98") (pin "2") (pinfunction "2_2") (pintype "passive"))
    )
    (net (code "86") (name "/LVDS_TWD_PC7") (class "Default")
      (node (ref "R111") (pin "2") (pinfunction "2_2") (pintype "passive"))
    )
    (net (code "87") (name "/MBUS1_AN_PC5") (class "Default")
      (node (ref "U5") (pin "G3") (pinfunction "PC5_G3") (pintype "bidirectional"))
    )
    (net (code "88") (name "/MBUS1_INT_PB7") (class "Default")
      (node (ref "U5") (pin "C20") (pinfunction "PB7_C20") (pintype "bidirectional"))
    )
    (net (code "89") (name "/MBUS1_MISO_PA17") (class "Default")
      (node (ref "R54") (pin "2") (pinfunction "2_2") (pintype "passive"))
    )
    (net (code "90") (name "/MBUS1_MOSI_PA18") (class "Default")
      (node (ref "R50") (pin "2") (pinfunction "2_2") (pintype "passive"))
    )
    (net (code "91") (name "/MBUS1_PWM_PB15") (class "Default")
      (node (ref "R80") (pin "2") (pinfunction "2_2") (pintype "passive"))
    )
    (net (code "92") (name "/MBUS1_RX{slash}CAN0_RX_PD9") (class "Default")
      (node (ref "U5") (pin "F14") (pinfunction "PD9_F14") (pintype "bidirectional"))
    )
    (net (code "93") (name "/MBUS1_SCK_PA16") (class "Default")
      (node (ref "R58") (pin "2") (pinfunction "2_2") (pintype "passive"))
    )
    (net (code "94") (name "/MBUS1_SPI_CS_PA15") (class "Default")
      (node (ref "R62") (pin "2") (pinfunction "2_2") (pintype "passive"))
    )
    (net (code "95") (name "/MBUS1_TWCK_PC6") (class "Default")
      (node (ref "R101") (pin "2") (pinfunction "2_2") (pintype "passive"))
    )
    (net (code "96") (name "/MBUS1_TWD_PC7") (class "Default")
      (node (ref "R115") (pin "2") (pinfunction "2_2") (pintype "passive"))
    )
    (net (code "97") (name "/MBUS1_TX{slash}CAN0_TX_PD8") (class "Default")
      (node (ref "U5") (pin "G14") (pinfunction "PD8_G14") (pintype "bidirectional"))
    )
    (net (code "98") (name "/MBUS2_AN_PC13") (class "Default")
      (node (ref "U5") (pin "D1") (pinfunction "PC13_D1") (pintype "bidirectional"))
    )
    (net (code "99") (name "/MBUS2_INT_PA22") (class "Default")
      (node (ref "U5") (pin "P10") (pinfunction "PA22_P10") (pintype "bidirectional"))
    )
    (net (code "100") (name "/MBUS2_MISO_PA17") (class "Default")
      (node (ref "R55") (pin "2") (pinfunction "2_2") (pintype "passive"))
    )
    (net (code "101") (name "/MBUS2_MOSI_PA18") (class "Default")
      (node (ref "R51") (pin "2") (pinfunction "2_2") (pintype "passive"))
    )
    (net (code "102") (name "/MBUS2_PWM_PB17") (class "Default")
      (node (ref "R88") (pin "2") (pinfunction "2_2") (pintype "passive"))
    )
    (net (code "103") (name "/MBUS2_RX{slash}CAN4_RX_PD17") (class "Default")
      (node (ref "U5") (pin "H13") (pinfunction "PD17_H13") (pintype "bidirectional"))
    )
    (net (code "104") (name "/MBUS2_SCK_PA16") (class "Default")
      (node (ref "R59") (pin "2") (pinfunction "2_2") (pintype "passive"))
    )
    (net (code "105") (name "/MBUS2_SPI_CS_PA14") (class "Default")
      (node (ref "R64") (pin "2") (pinfunction "2_2") (pintype "passive"))
    )
    (net (code "106") (name "/MBUS2_TWCK_PC6") (class "Default")
      (node (ref "R103") (pin "2") (pinfunction "2_2") (pintype "passive"))
    )
    (net (code "107") (name "/MBUS2_TWD_PC7") (class "Default")
      (node (ref "R117") (pin "2") (pinfunction "2_2") (pintype "passive"))
    )
    (net (code "108") (name "/MBUS2_TX{slash}CAN4_TX_PD16") (class "Default")
      (node (ref "U5") (pin "E18") (pinfunction "PD16_E18") (pintype "bidirectional"))
    )
    (net (code "109") (name "/MBUS_nRST_PC9") (class "Default")
      (node (ref "U5") (pin "D6") (pinfunction "PC9_D6") (pintype "bidirectional"))
    )
    (net (code "110") (name "/MCP16502_INT_PC2") (class "Default")
      (node (ref "U5") (pin "D7") (pinfunction "PC2_D7") (pintype "bidirectional"))
    )
    (net (code "111") (name "/MCP16502_TWCK_PB19") (class "Default")
      (node (ref "R77") (pin "2") (pinfunction "2_2") (pintype "passive"))
    )
    (net (code "112") (name "/MCP16502_TWD_PB20") (class "Default")
      (node (ref "R87") (pin "2") (pinfunction "2_2") (pintype "passive"))
    )
    (net (code "113") (name "/MIPI_ENABLE_PB18") (class "Default")
      (node (ref "R75") (pin "2") (pinfunction "2_2") (pintype "passive"))
    )
    (net (code "114") (name "/MIPI_IRQ_PB16") (class "Default")
      (node (ref "R72") (pin "2") (pinfunction "2_2") (pintype "passive"))
    )
    (net (code "115") (name "/MIPI_PWM_PB14") (class "Default")
      (node (ref "R67") (pin "2") (pinfunction "2_2") (pintype "passive"))
    )
    (net (code "116") (name "/MIPI_TWCK_PC6") (class "Default")
      (node (ref "R100") (pin "2") (pinfunction "2_2") (pintype "passive"))
    )
    (net (code "117") (name "/MIPI_TWD_PC7") (class "Default")
      (node (ref "R113") (pin "2") (pinfunction "2_2") (pintype "passive"))
    )
    (net (code "118") (name "/NAND_ALE_PA1") (class "Default")
      (node (ref "U5") (pin "V17") (pinfunction "PA1_V17") (pintype "bidirectional"))
    )
    (net (code "119") (name "/NAND_CLE_PA2") (class "Default")
      (node (ref "U5") (pin "R14") (pinfunction "PA2_R14") (pintype "bidirectional"))
    )
    (net (code "120") (name "/NAND_CS_PA13") (class "Default")
      (node (ref "U5") (pin "P11") (pinfunction "PA13_P11") (pintype "bidirectional"))
    )
    (net (code "121") (name "/NAND_D0_PA3") (class "Default")
      (node (ref "U5") (pin "T18") (pinfunction "PA3_T18") (pintype "bidirectional"))
    )
    (net (code "122") (name "/NAND_D1_PA4") (class "Default")
      (node (ref "U5") (pin "P16") (pinfunction "PA4_P16") (pintype "bidirectional"))
    )
    (net (code "123") (name "/NAND_D2_PA9") (class "Default")
      (node (ref "U5") (pin "U14") (pinfunction "PA9_U14") (pintype "bidirectional"))
    )
    (net (code "124") (name "/NAND_D3_PA10") (class "Default")
      (node (ref "U5") (pin "R12") (pinfunction "PA10_R12") (pintype "bidirectional"))
    )
    (net (code "125") (name "/NAND_D4_PA5") (class "Default")
      (node (ref "U5") (pin "V16") (pinfunction "PA5_V16") (pintype "bidirectional"))
    )
    (net (code "126") (name "/NAND_D5_PA6") (class "Default")
      (node (ref "U5") (pin "T14") (pinfunction "PA6_T14") (pintype "bidirectional"))
    )
    (net (code "127") (name "/NAND_D6_PA7") (class "Default")
      (node (ref "U5") (pin "P15") (pinfunction "PA7_P15") (pintype "bidirectional"))
    )
    (net (code "128") (name "/NAND_D7_PA8") (class "Default")
      (node (ref "U5") (pin "R13") (pinfunction "PA8_R13") (pintype "bidirectional"))
    )
    (net (code "129") (name "/NAND_RDY_PA11") (class "Default")
      (node (ref "U5") (pin "P12") (pinfunction "PA11_P12") (pintype "bidirectional"))
    )
    (net (code "130") (name "/NAND_RE_PA12") (class "Default")
      (node (ref "U5") (pin "W15") (pinfunction "PA12_W15") (pintype "bidirectional"))
    )
    (net (code "131") (name "/NAND_WE_PA0") (class "Default")
      (node (ref "U5") (pin "U18") (pinfunction "PA0_U18") (pintype "bidirectional"))
    )
    (net (code "132") (name "/PAC1934_INT_PB31") (class "Default")
      (node (ref "R112") (pin "2") (pinfunction "2_2") (pintype "passive"))
    )
    (net (code "133") (name "/PAC1934_TWCK_PB19") (class "Default")
      (node (ref "R79") (pin "2") (pinfunction "2_2") (pintype "passive"))
    )
    (net (code "134") (name "/PAC1934_TWD_PB20") (class "Default")
      (node (ref "R89") (pin "2") (pinfunction "2_2") (pintype "passive"))
    )
    (net (code "135") (name "/PB14") (class "Default")
      (node (ref "R67") (pin "1") (pinfunction "1_1") (pintype "passive"))
      (node (ref "R69") (pin "1") (pinfunction "1_1") (pintype "passive"))
      (node (ref "U5") (pin "N15") (pinfunction "PB14_N15") (pintype "bidirectional"))
    )
    (net (code "136") (name "/PB15") (class "Default")
      (node (ref "R78") (pin "1") (pinfunction "1_1") (pintype "passive"))
      (node (ref "R80") (pin "1") (pinfunction "1_1") (pintype "passive"))
      (node (ref "R82") (pin "1") (pinfunction "1_1") (pintype "passive"))
      (node (ref "U5") (pin "M15") (pinfunction "PB15_M15") (pintype "bidirectional"))
    )
    (net (code "137") (name "/PB16") (class "Default")
      (node (ref "R72") (pin "1") (pinfunction "1_1") (pintype "passive"))
      (node (ref "R74") (pin "1") (pinfunction "1_1") (pintype "passive"))
      (node (ref "U5") (pin "N20") (pinfunction "PB16_N20") (pintype "bidirectional"))
    )
    (net (code "138") (name "/PB17") (class "Default")
      (node (ref "R86") (pin "1") (pinfunction "1_1") (pintype "passive"))
      (node (ref "R88") (pin "1") (pinfunction "1_1") (pintype "passive"))
      (node (ref "R90") (pin "1") (pinfunction "1_1") (pintype "passive"))
      (node (ref "U5") (pin "M14") (pinfunction "PB17_M14") (pintype "bidirectional"))
    )
    (net (code "139") (name "/PB18") (class "Default")
      (node (ref "R75") (pin "1") (pinfunction "1_1") (pintype "passive"))
      (node (ref "R76") (pin "1") (pinfunction "1_1") (pintype "passive"))
      (node (ref "U5") (pin "N21") (pinfunction "PB18_N21") (pintype "bidirectional"))
    )
    (net (code "140") (name "/PB31") (class "Default")
      (node (ref "R112") (pin "1") (pinfunction "1_1") (pintype "passive"))
      (node (ref "R114") (pin "1") (pinfunction "1_1") (pintype "passive"))
      (node (ref "R116") (pin "2") (pinfunction "2_2") (pintype "passive"))
      (node (ref "U5") (pin "C5") (pinfunction "PB31_C5") (pintype "bidirectional"))
    )
    (net (code "141") (name "/PC0") (class "Default")
      (node (ref "R119") (pin "1") (pinfunction "1_1") (pintype "passive"))
      (node (ref "R121") (pin "2") (pinfunction "2_2") (pintype "passive"))
      (node (ref "U5") (pin "J8") (pinfunction "PC0_J8") (pintype "bidirectional"))
    )
    (net (code "142") (name "/PC18") (class "Default")
      (node (ref "R102") (pin "1") (pinfunction "1_1") (pintype "passive"))
      (node (ref "R104") (pin "1") (pinfunction "1_1") (pintype "passive"))
      (node (ref "U5") (pin "F7") (pinfunction "PC18_F7") (pintype "bidirectional"))
    )
    (net (code "143") (name "/PC19") (class "Default")
      (node (ref "R108") (pin "1") (pinfunction "1_1") (pintype "passive"))
      (node (ref "R109") (pin "1") (pinfunction "1_1") (pintype "passive"))
      (node (ref "U5") (pin "D5") (pinfunction "PC19_D5") (pintype "bidirectional"))
    )
    (net (code "144") (name "/PC27") (class "Default")
      (node (ref "R93") (pin "1") (pinfunction "1_1") (pintype "passive"))
      (node (ref "R94") (pin "1") (pinfunction "1_1") (pintype "passive"))
      (node (ref "U5") (pin "C15") (pinfunction "PC27_C15") (pintype "bidirectional"))
    )
    (net (code "145") (name "/PC28") (class "Default")
      (node (ref "R95") (pin "1") (pinfunction "1_1") (pintype "passive"))
      (node (ref "R96") (pin "1") (pinfunction "1_1") (pintype "passive"))
      (node (ref "U5") (pin "D16") (pinfunction "PC28_D16") (pintype "bidirectional"))
    )
    (net (code "146") (name "/PC29") (class "Default")
      (node (ref "R97") (pin "1") (pinfunction "1_1") (pintype "passive"))
      (node (ref "R99") (pin "1") (pinfunction "1_1") (pintype "passive"))
      (node (ref "U5") (pin "B16") (pinfunction "PC29_B16") (pintype "bidirectional"))
    )
    (net (code "147") (name "/PD1") (class "Default")
      (node (ref "R122") (pin "1") (pinfunction "1_1") (pintype "passive"))
      (node (ref "R123") (pin "1") (pinfunction "1_1") (pintype "passive"))
      (node (ref "U5") (pin "A18") (pinfunction "PD1_A18") (pintype "bidirectional"))
    )
    (net (code "148") (name "/PD2") (class "Default")
      (node (ref "R124") (pin "1") (pinfunction "1_1") (pintype "passive"))
      (node (ref "R125") (pin "1") (pinfunction "1_1") (pintype "passive"))
      (node (ref "U5") (pin "G13") (pinfunction "PD2_G13") (pintype "bidirectional"))
    )
    (net (code "149") (name "/PD20") (class "Default")
      (node (ref "R126") (pin "1") (pinfunction "1_1") (pintype "passive"))
      (node (ref "R127") (pin "1") (pinfunction "1_1") (pintype "passive"))
      (node (ref "U5") (pin "J12") (pinfunction "PD20_J12") (pintype "bidirectional"))
    )
    (net (code "150") (name "/PIOBU0_WAKE") (class "Default")
      (node (ref "U5") (pin "J10") (pinfunction "PIOBU0_J10") (pintype "input"))
    )
    (net (code "151") (name "/PIOBU1_WAKE") (class "Default")
      (node (ref "U5") (pin "A5") (pinfunction "PIOBU1_A5") (pintype "input"))
    )
    (net (code "152") (name "/PIOBU2") (class "Default")
      (node (ref "U5") (pin "D8") (pinfunction "PIOBU2_D8") (pintype "input"))
    )
    (net (code "153") (name "/PIOBU3") (class "Default")
      (node (ref "U5") (pin "A4") (pinfunction "PIOBU3_A4") (pintype "input"))
    )
    (net (code "154") (name "/QSPI0_CS_PB12") (class "Default")
      (node (ref "U5") (pin "P18") (pinfunction "PB12_P18") (pintype "bidirectional"))
    )
    (net (code "155") (name "/QSPI0_IO0_PB11") (class "Default")
      (node (ref "U5") (pin "R19") (pinfunction "PB11_R19") (pintype "bidirectional"))
    )
    (net (code "156") (name "/QSPI0_IO1_PB10") (class "Default")
      (node (ref "U5") (pin "P17") (pinfunction "PB10_P17") (pintype "bidirectional"))
    )
    (net (code "157") (name "/QSPI0_IO2_PB9") (class "Default")
      (node (ref "U5") (pin "R18") (pinfunction "PB9_R18") (pintype "bidirectional"))
    )
    (net (code "158") (name "/QSPI0_IO3_PB8") (class "Default")
      (node (ref "U5") (pin "T19") (pinfunction "PB8_T19") (pintype "bidirectional"))
    )
    (net (code "159") (name "/QSPI0_SCK_PB13") (class "Default")
      (node (ref "U5") (pin "N14") (pinfunction "PB13_N14") (pintype "bidirectional"))
    )
    (net (code "160") (name "/RPI_GPCLK0_PB31") (class "Default")
      (node (ref "R114") (pin "2") (pinfunction "2_2") (pintype "passive"))
    )
    (net (code "161") (name "/RPI_GPCLK1_PD20") (class "Default")
      (node (ref "R127") (pin "2") (pinfunction "2_2") (pintype "passive"))
    )
    (net (code "162") (name "/RPI_GPCLK2_PC0") (class "Default")
      (node (ref "R119") (pin "2") (pinfunction "2_2") (pintype "passive"))
    )
    (net (code "163") (name "/RPI_GPIO16_PC18") (class "Default")
      (node (ref "R104") (pin "2") (pinfunction "2_2") (pintype "passive"))
    )
    (net (code "164") (name "/RPI_GPIO17_PC3") (class "Default")
      (node (ref "U5") (pin "G8") (pinfunction "PC3_G8") (pintype "bidirectional"))
    )
    (net (code "165") (name "/RPI_GPIO22_PD1") (class "Default")
      (node (ref "R123") (pin "2") (pinfunction "2_2") (pintype "passive"))
    )
    (net (code "166") (name "/RPI_GPIO23_PD2") (class "Default")
      (node (ref "R125") (pin "2") (pinfunction "2_2") (pintype "passive"))
    )
    (net (code "167") (name "/RPI_GPIO24_PC12") (class "Default")
      (node (ref "U5") (pin "H5") (pinfunction "PC12_H5") (pintype "bidirectional"))
    )
    (net (code "168") (name "/RPI_GPIO25_PC11") (class "Default")
      (node (ref "U5") (pin "C1") (pinfunction "PC11_C1") (pintype "bidirectional"))
    )
    (net (code "169") (name "/RPI_GPIO26_PC19") (class "Default")
      (node (ref "R109") (pin "2") (pinfunction "2_2") (pintype "passive"))
    )
    (net (code "170") (name "/RPI_GPIO27_PC4") (class "Default")
      (node (ref "U5") (pin "C2") (pinfunction "PC4_C2") (pintype "bidirectional"))
    )
    (net (code "171") (name "/RPI_I2S_CK_PC16") (class "Default")
      (node (ref "U5") (pin "H4") (pinfunction "PC16_H4") (pintype "bidirectional"))
    )
    (net (code "172") (name "/RPI_I2S_DIN0_PC14") (class "Default")
      (node (ref "U5") (pin "J7") (pinfunction "PC14_J7") (pintype "bidirectional"))
    )
    (net (code "173") (name "/RPI_I2S_DOUT0_PC17") (class "Default")
      (node (ref "U5") (pin "D4") (pinfunction "PC17_D4") (pintype "bidirectional"))
    )
    (net (code "174") (name "/RPI_I2S_WS_PC15") (class "Default")
      (node (ref "U5") (pin "F3") (pinfunction "PC15_F3") (pintype "bidirectional"))
    )
    (net (code "175") (name "/RPI_MISO_PA17") (class "Default")
      (node (ref "R56") (pin "2") (pinfunction "2_2") (pintype "passive"))
    )
    (net (code "176") (name "/RPI_MOSI_PA18") (class "Default")
      (node (ref "R52") (pin "2") (pinfunction "2_2") (pintype "passive"))
    )
    (net (code "177") (name "/RPI_NPCS0_PA19") (class "Default")
      (node (ref "R66") (pin "2") (pinfunction "2_2") (pintype "passive"))
    )
    (net (code "178") (name "/RPI_NPCS1_PA20") (class "Default")
      (node (ref "R70") (pin "2") (pinfunction "2_2") (pintype "passive"))
    )
    (net (code "179") (name "/RPI_PWM0_PB15") (class "Default")
      (node (ref "R82") (pin "2") (pinfunction "2_2") (pintype "passive"))
    )
    (net (code "180") (name "/RPI_PWM1_PB17") (class "Default")
      (node (ref "R90") (pin "2") (pinfunction "2_2") (pintype "passive"))
    )
    (net (code "181") (name "/RPI_RXD_PA23") (class "Default")
      (node (ref "U5") (pin "AA20") (pinfunction "PA23_AA20") (pintype "bidirectional"))
    )
    (net (code "182") (name "/RPI_SPCK_PA16") (class "Default")
      (node (ref "R60") (pin "2") (pinfunction "2_2") (pintype "passive"))
    )
    (net (code "183") (name "/RPI_TWCK_PC6") (class "Default")
      (node (ref "R105") (pin "2") (pinfunction "2_2") (pintype "passive"))
    )
    (net (code "184") (name "/RPI_TWD_PC7") (class "Default")
      (node (ref "R118") (pin "2") (pinfunction "2_2") (pintype "passive"))
    )
    (net (code "185") (name "/RPI_TXD_PA24") (class "Default")
      (node (ref "U5") (pin "P9") (pinfunction "PA24_P9") (pintype "bidirectional"))
    )
    (net (code "186") (name "/SDMMC1_1V8SEL_PB30") (class "Default")
      (node (ref "U5") (pin "A2") (pinfunction "PB30_A2") (pintype "bidirectional"))
    )
    (net (code "187") (name "/SDMMC1_CD_PB29") (class "Default")
      (node (ref "U5") (pin "G4") (pinfunction "PB29_G4") (pintype "bidirectional"))
    )
    (net (code "188") (name "/SDMMC1_CK_PB23") (class "Default")
      (node (ref "U5") (pin "D14") (pinfunction "PB23_D14") (pintype "bidirectional"))
    )
    (net (code "189") (name "/SDMMC1_CMD_PB22") (class "Default")
      (node (ref "U5") (pin "C14") (pinfunction "PB22_C14") (pintype "bidirectional"))
    )
    (net (code "190") (name "/SDMMC1_DAT0_PB24") (class "Default")
      (node (ref "U5") (pin "B15") (pinfunction "PB24_B15") (pintype "bidirectional"))
    )
    (net (code "191") (name "/SDMMC1_DAT1_PB25") (class "Default")
      (node (ref "U5") (pin "A13") (pinfunction "PB25_A13") (pintype "bidirectional"))
    )
    (net (code "192") (name "/SDMMC1_DAT2_PB26") (class "Default")
      (node (ref "U5") (pin "A15") (pinfunction "PB26_A15") (pintype "bidirectional"))
    )
    (net (code "193") (name "/SDMMC1_DAT3_PB27") (class "Default")
      (node (ref "U5") (pin "C11") (pinfunction "PB27_C11") (pintype "bidirectional"))
    )
    (net (code "194") (name "/SDMMC1_NRST_PB21") (class "Default")
      (node (ref "U5") (pin "D15") (pinfunction "PB21_D15") (pintype "bidirectional"))
    )
    (net (code "195") (name "/SDMMC1_WP_PB28") (class "Default")
      (node (ref "U5") (pin "C3") (pinfunction "PB28_C3") (pintype "bidirectional"))
    )
    (net (code "196") (name "/SDMMC2_CK_PC28") (class "Default")
      (node (ref "R95") (pin "2") (pinfunction "2_2") (pintype "passive"))
    )
    (net (code "197") (name "/SDMMC2_CMD_PC27") (class "Default")
      (node (ref "R93") (pin "2") (pinfunction "2_2") (pintype "passive"))
    )
    (net (code "198") (name "/SDMMC2_DAT0_PC29") (class "Default")
      (node (ref "R97") (pin "2") (pinfunction "2_2") (pintype "passive"))
    )
    (net (code "199") (name "/SDMMC2_DAT1_PC30") (class "Default")
      (node (ref "U5") (pin "D17") (pinfunction "PC30_D17") (pintype "bidirectional"))
    )
    (net (code "200") (name "/SDMMC2_DAT2_PC31") (class "Default")
      (node (ref "U5") (pin "A16") (pinfunction "PC31_A16") (pintype "bidirectional"))
    )
    (net (code "201") (name "/SDMMC2_DAT3_PD0") (class "Default")
      (node (ref "U5") (pin "C16") (pinfunction "PD0_C16") (pintype "bidirectional"))
    )
    (net (code "202") (name "/USBA_VBUS_DETECT_PC8") (class "Default")
      (node (ref "U5") (pin "E6") (pinfunction "PC8_E6") (pintype "bidirectional"))
    )
    (net (code "203") (name "/USBB_EN_5V_PC20") (class "Default")
      (node (ref "U5") (pin "C6") (pinfunction "PC20_C6") (pintype "bidirectional"))
    )
    (net (code "204") (name "/USBB_OVCUR_PC18") (class "Default")
      (node (ref "R102") (pin "2") (pinfunction "2_2") (pintype "passive"))
    )
    (net (code "205") (name "/USBC_EN_5V_PC21") (class "Default")
      (node (ref "U5") (pin "F8") (pinfunction "PC21_F8") (pintype "bidirectional"))
    )
    (net (code "206") (name "/USBC_OVCUR_PC19") (class "Default")
      (node (ref "R108") (pin "2") (pinfunction "2_2") (pintype "passive"))
    )
    (net (code "207") (name "/USER_BUTTON_PC10") (class "Default")
      (node (ref "U5") (pin "H7") (pinfunction "PC10_H7") (pintype "bidirectional"))
    )
    (net (code "208") (name "/WIFI_IRQN_PD1") (class "Default")
      (node (ref "R122") (pin "2") (pinfunction "2_2") (pintype "passive"))
    )
    (net (code "209") (name "/WIFI_RSTN_PD20") (class "Default")
      (node (ref "R126") (pin "2") (pinfunction "2_2") (pintype "passive"))
    )
    (net (code "210") (name "/WIFI_SPI_MISO_PC28") (class "Default")
      (node (ref "R96") (pin "2") (pinfunction "2_2") (pintype "passive"))
    )
    (net (code "211") (name "/WIFI_SPI_MOSI_PC27") (class "Default")
      (node (ref "R94") (pin "2") (pinfunction "2_2") (pintype "passive"))
    )
    (net (code "212") (name "/WIFI_SPI_SCK_PC29") (class "Default")
      (node (ref "R99") (pin "2") (pinfunction "2_2") (pintype "passive"))
    )
    (net (code "213") (name "/WIFI_TWCK_PC6") (class "Default")
      (node (ref "R107") (pin "2") (pinfunction "2_2") (pintype "passive"))
    )
    (net (code "214") (name "/WIFI_TWD_PC7") (class "Default")
      (node (ref "R120") (pin "2") (pinfunction "2_2") (pintype "passive"))
    )
    (net (code "215") (name "/WIFI_TWI_IRQ_PD2") (class "Default")
      (node (ref "R124") (pin "2") (pinfunction "2_2") (pintype "passive"))
    )
    (net (code "216") (name "/WIFI_WAKE_HOST_PD4") (class "Default")
      (node (ref "U5") (pin "G12") (pinfunction "PD4_G12") (pintype "bidirectional"))
    )
    (net (code "217") (name "VDD_3V3") (class "Default")
      (node (ref "R106") (pin "1") (pinfunction "1_1") (pintype "passive"))
      (node (ref "R110") (pin "1") (pinfunction "1_1") (pintype "passive"))
      (node (ref "R63") (pin "2") (pinfunction "2_2") (pintype "passive"))
      (node (ref "R65") (pin "2") (pinfunction "2_2") (pintype "passive"))
      (node (ref "R68") (pin "2") (pinfunction "2_2") (pintype "passive"))
      (node (ref "R73") (pin "2") (pinfunction "2_2") (pintype "passive"))
      (node (ref "R83") (pin "1") (pinfunction "1_1") (pintype "passive"))
      (node (ref "R85") (pin "1") (pinfunction "1_1") (pintype "passive"))
    )
  )
)
